# Drive.net
KiCad netlist of a schematic drawn in Altium Designer
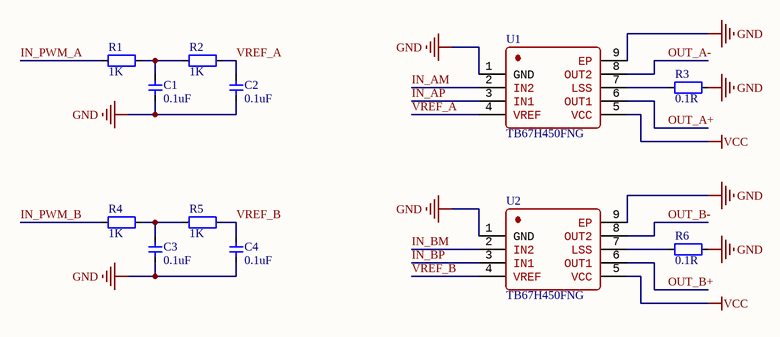
[diagram p0: Drive.SchDoc]

(export (version "E")
  (design (tool "Eeschema 10.0.6"))
  (components
    (comp (ref "C1")
      (value "0.1uF")
      (footprint "CAP_0402")
      (description "Capacitor")
      (libsource (lib "MyPcbLib") (part "电容-0402"))
    )
    (comp (ref "C2")
      (value "0.1uF")
      (footprint "CAP_0402")
      (description "Capacitor")
      (libsource (lib "MyPcbLib") (part "电容-0402"))
    )
    (comp (ref "C3")
      (value "0.1uF")
      (footprint "CAP_0402")
      (description "Capacitor")
      (libsource (lib "MyPcbLib") (part "电容-0402"))
    )
    (comp (ref "C4")
      (value "0.1uF")
      (footprint "CAP_0402")
      (description "Capacitor")
      (libsource (lib "MyPcbLib") (part "电容-0402"))
    )
    (comp (ref "R1")
      (value "1K")
      (footprint "RES_0402")
      (description "Resistor")
      (libsource (lib "MyPcbLib") (part "电阻-0402"))
    )
    (comp (ref "R2")
      (value "1K")
      (footprint "RES_0402")
      (description "Resistor")
      (libsource (lib "MyPcbLib") (part "电阻-0402"))
    )
    (comp (ref "R3")
      (value "0.1R")
      (footprint "1206-RES")
      (description "Resistor")
      (libsource (lib "MyPcbLib") (part "电阻-1206"))
    )
    (comp (ref "R4")
      (value "1K")
      (footprint "RES_0402")
      (description "Resistor")
      (libsource (lib "MyPcbLib") (part "电阻-0402"))
    )
    (comp (ref "R5")
      (value "1K")
      (footprint "RES_0402")
      (description "Resistor")
      (libsource (lib "MyPcbLib") (part "电阻-0402"))
    )
    (comp (ref "R6")
      (value "0.1R")
      (footprint "1206-RES")
      (description "Resistor")
      (libsource (lib "MyPcbLib") (part "电阻-1206"))
    )
    (comp (ref "U1")
      (value "TB67H450FNG")
      (footprint "SO-8-PAD")
      (description "PWM Chopper Type DC Brushed Motor Driver")
      (libsource (lib "MyPcbLib") (part "TB67H450FNG"))
    )
    (comp (ref "U2")
      (value "TB67H450FNG")
      (footprint "SO-8-PAD")
      (description "PWM Chopper Type DC Brushed Motor Driver")
      (libsource (lib "MyPcbLib") (part "TB67H450FNG"))
    )
  )
  (nets
    (net (code "1") (name "/IN_AM") (class "Default")
      (node (ref "U1") (pin "2") (pinfunction "IN2_2") (pintype "passive"))
    )
    (net (code "2") (name "/IN_AP") (class "Default")
      (node (ref "U1") (pin "3") (pinfunction "IN1_3") (pintype "passive"))
    )
    (net (code "3") (name "/IN_BM") (class "Default")
      (node (ref "U2") (pin "2") (pinfunction "IN2_2") (pintype "passive"))
    )
    (net (code "4") (name "/IN_BP") (class "Default")
      (node (ref "U2") (pin "3") (pinfunction "IN1_3") (pintype "passive"))
    )
    (net (code "5") (name "/IN_PWM_A") (class "Default")
      (node (ref "R1") (pin "1") (pinfunction "1_1") (pintype "passive"))
    )
    (net (code "6") (name "/IN_PWM_B") (class "Default")
      (node (ref "R4") (pin "1") (pinfunction "1_1") (pintype "passive"))
    )
    (net (code "7") (name "/OUT_A+") (class "Default")
      (node (ref "U1") (pin "6") (pinfunction "OUT1_6") (pintype "passive"))
    )
    (net (code "8") (name "/OUT_A-") (class "Default")
      (node (ref "U1") (pin "8") (pinfunction "OUT2_8") (pintype "passive"))
    )
    (net (code "9") (name "/OUT_B+") (class "Default")
      (node (ref "U2") (pin "6") (pinfunction "OUT1_6") (pintype "passive"))
    )
    (net (code "10") (name "/OUT_B-") (class "Default")
      (node (ref "U2") (pin "8") (pinfunction "OUT2_8") (pintype "passive"))
    )
    (net (code "11") (name "/VREF_A") (class "Default")
      (node (ref "C2") (pin "2") (pinfunction "2_2") (pintype "passive"))
      (node (ref "R2") (pin "2") (pinfunction "2_2") (pintype "passive"))
      (node (ref "U1") (pin "4") (pinfunction "VREF_4") (pintype "passive"))
    )
    (net (code "12") (name "/VREF_B") (class "Default")
      (node (ref "C4") (pin "2") (pinfunction "2_2") (pintype "passive"))
      (node (ref "R5") (pin "2") (pinfunction "2_2") (pintype "passive"))
      (node (ref "U2") (pin "4") (pinfunction "VREF_4") (pintype "passive"))
    )
    (net (code "13") (name "GND") (class "Default")
      (node (ref "C1") (pin "1") (pinfunction "1_1") (pintype "passive"))
      (node (ref "C2") (pin "1") (pinfunction "1_1") (pintype "passive"))
      (node (ref "C3") (pin "1") (pinfunction "1_1") (pintype "passive"))
      (node (ref "C4") (pin "1") (pinfunction "1_1") (pintype "passive"))
      (node (ref "R3") (pin "2") (pinfunction "2_2") (pintype "passive"))
      (node (ref "R6") (pin "2") (pinfunction "2_2") (pintype "passive"))
      (node (ref "U1") (pin "1") (pinfunction "GND_1") (pintype "passive"))
      (node (ref "U1") (pin "9") (pinfunction "EP_9") (pintype "passive"))
      (node (ref "U2") (pin "1") (pinfunction "GND_1") (pintype "passive"))
      (node (ref "U2") (pin "9") (pinfunction "EP_9") (pintype "passive"))
    )
    (net (code "14") (name "Net-(C1-Pad2)") (class "Default")
      (node (ref "C1") (pin "2") (pinfunction "2_2") (pintype "passive"))
      (node (ref "R1") (pin "2") (pinfunction "2_2") (pintype "passive"))
      (node (ref "R2") (pin "1") (pinfunction "1_1") (pintype "passive"))
    )
    (net (code "15") (name "Net-(C3-Pad2)") (class "Default")
      (node (ref "C3") (pin "2") (pinfunction "2_2") (pintype "passive"))
      (node (ref "R4") (pin "2") (pinfunction "2_2") (pintype "passive"))
      (node (ref "R5") (pin "1") (pinfunction "1_1") (pintype "passive"))
    )
    (net (code "16") (name "Net-(U1-LSS)") (class "Default")
      (node (ref "R3") (pin "1") (pinfunction "1_1") (pintype "passive"))
      (node (ref "U1") (pin "7") (pinfunction "LSS_7") (pintype "passive"))
    )
    (net (code "17") (name "Net-(U2-LSS)") (class "Default")
      (node (ref "R6") (pin "1") (pinfunction "1_1") (pintype "passive"))
      (node (ref "U2") (pin "7") (pinfunction "LSS_7") (pintype "passive"))
    )
    (net (code "18") (name "VCC") (class "Default")
      (node (ref "U1") (pin "5") (pinfunction "VCC_5") (pintype "passive"))
      (node (ref "U2") (pin "5") (pinfunction "VCC_5") (pintype "passive"))
    )
  )
)
